# edrschematic.net
KiCad netlist of a schematic drawn in Altium Designer
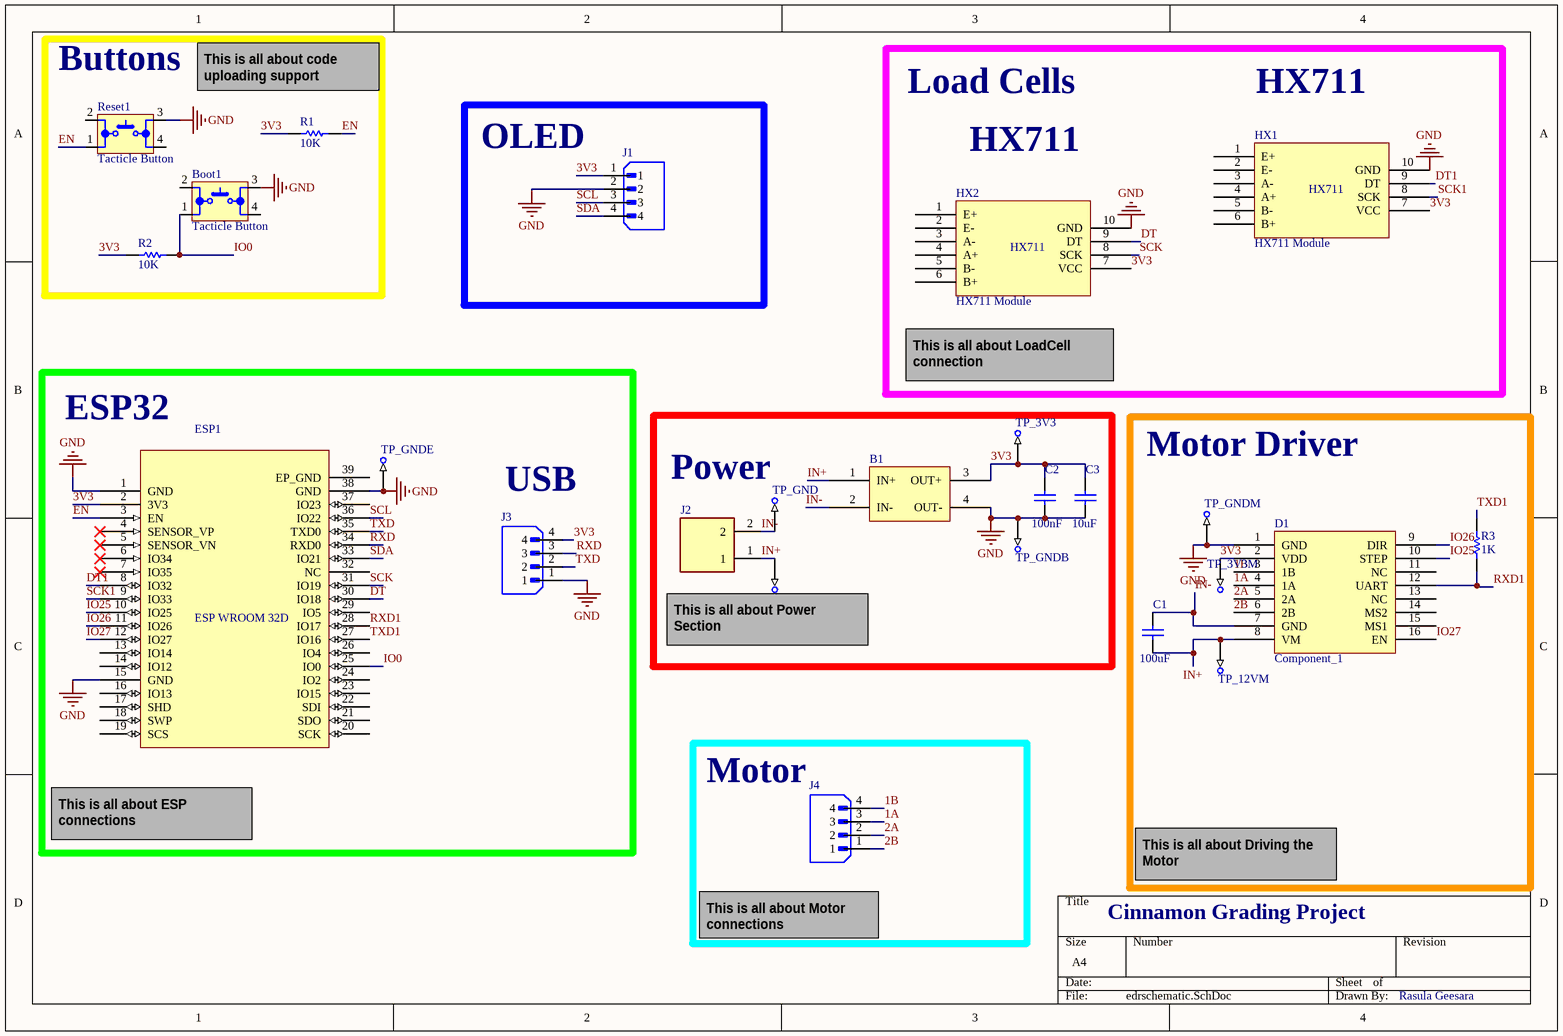
[diagram p0: edrschematic.SchDoc]

(export (version "E")
  (design (tool "Eeschema 10.0.6"))
  (components
    (comp (ref "B1")
      (value "LM2596s Buck")
      (footprint "LM2596s buck:PCBComponent_1")
      (description "buck converter")
      (libsource (lib "LM2596s buck") (part "LM2596s Buck"))
    )
    (comp (ref "Boot1")
      (value "Tacticle Button")
      (footprint "1825910-6_BUTTON")
      (description "SWITCH TACTILE SPST-NO 0.05A 24V")
      (fields
        (field (name "MANUFACTURER") "TE Connectivity Alcoswitch")
        (field (name "MANUFACTURER PART NUMBER") "1825910-6")
      )
      (libsource (lib "Tactile_Switch_Integrated_Library") (part "1825910-6"))
    )
    (comp (ref "C1")
      (value "100uF")
      (footprint "RAD-0.3")
      (description "Capacitor")
      (fields (field (name "Comment") "Cap") (field (name "PUBLISHER") "Altium Limited"))
      (libsource (lib "Miscellaneous Devices") (part "Cap"))
    )
    (comp (ref "C2")
      (value "100nF")
      (footprint "RAD-0.3")
      (description "Capacitor")
      (fields (field (name "Comment") "Cap") (field (name "PUBLISHER") "Altium Limited"))
      (libsource (lib "Miscellaneous Devices") (part "Cap"))
    )
    (comp (ref "C3")
      (value "10uF")
      (footprint "RAD-0.3")
      (description "Capacitor")
      (fields (field (name "Comment") "Cap") (field (name "PUBLISHER") "Altium Limited"))
      (libsource (lib "Miscellaneous Devices") (part "Cap"))
    )
    (comp (ref "D1")
      (value "Component_1")
      (footprint "stepper driver:MODULE_TMC2208_SILENTSTEPSTICK")
      (libsource (lib "stepper driver") (part "Component_1"))
    )
    (comp (ref "ESP1")
      (value "Component_1")
      (footprint "ESP32-WROOM-32D")
      (libsource (lib "Integrated_Library3") (part "Component_1"))
    )
    (comp (ref "HX1")
      (value "HX711 Module")
      (footprint "HX711_NEW:HX711")
      (libsource (lib "Integrated_Library2") (part "HX711"))
    )
    (comp (ref "HX2")
      (value "HX711 Module")
      (footprint "HX711_NEW:HX711")
      (libsource (lib "Integrated_Library2") (part "HX711"))
    )
    (comp (ref "J1")
      (value "B4B-XH-A(LF)(SN)")
      (footprint "B4B-XH-A_LF__SN_:JST_B4B-XH-A(LF)(SN)")
      (description "Connector Header Through Hole 4 position 0.098 (2.50mm)")
      (fields (field (name "MF") "JST Sales"))
      (libsource (lib "") (part "B4B-XH-A(LF)(SN)_1"))
    )
    (comp (ref "J2")
      (value "KF301-2P")
      (footprint "HANDSON_KF301-2P")
      (description "2 Pin Terminal Block 5mm Pitch")
      (fields (field (name "MF") "Handson Technology"))
      (libsource (lib "KF301-2P") (part "KF301-2P"))
    )
    (comp (ref "J3")
      (value "B4B-XH-A(LF)(SN)")
      (footprint "B4B-XH-A_LF__SN_:JST_B4B-XH-A(LF)(SN)")
      (description "Connector Header Through Hole 4 position 0.098 (2.50mm)")
      (fields (field (name "MF") "JST Sales"))
      (libsource (lib "B4B-XH-A_LF__SN_") (part "B4B-XH-A(LF)(SN)"))
    )
    (comp (ref "J4")
      (value "B4B-XH-A(LF)(SN)")
      (footprint "B4B-XH-A_LF__SN_:JST_B4B-XH-A(LF)(SN)")
      (description "Connector Header Through Hole 4 position 0.098 (2.50mm)")
      (fields (field (name "MF") "JST Sales"))
      (libsource (lib "B4B-XH-A_LF__SN_") (part "B4B-XH-A(LF)(SN)"))
    )
    (comp (ref "R1")
      (value "10K")
      (footprint "AXIAL-0.3")
      (description "Resistor")
      (fields (field (name "Comment") "Res1") (field (name "PUBLISHER") "Altium Limited"))
      (libsource (lib "Miscellaneous Devices") (part "Res1"))
    )
    (comp (ref "R2")
      (value "10K")
      (footprint "AXIAL-0.3")
      (description "Resistor")
      (fields (field (name "Comment") "Res1") (field (name "PUBLISHER") "Altium Limited"))
      (libsource (lib "Miscellaneous Devices") (part "Res1"))
    )
    (comp (ref "R3")
      (value "1K")
      (footprint "AXIAL-0.3")
      (description "Resistor")
      (fields (field (name "Comment") "Res1") (field (name "PUBLISHER") "Altium Limited"))
      (libsource (lib "Miscellaneous Devices") (part "Res1"))
    )
    (comp (ref "Reset1")
      (value "Tacticle Button")
      (footprint "1825910-6_BUTTON")
      (description "SWITCH TACTILE SPST-NO 0.05A 24V")
      (fields
        (field (name "MANUFACTURER") "TE Connectivity Alcoswitch")
        (field (name "MANUFACTURER PART NUMBER") "1825910-6")
      )
      (libsource (lib "Tactile_Switch_Integrated_Library") (part "1825910-6"))
    )
    (comp (ref "TP_3V3")
      (value "net?")
      (footprint "MY_Testpad1")
      (description "Test point")
      (fields (field (name "ASID PART NUMBER") "Test Point-AS"))
      (libsource (lib "Mylib+Rev+4") (part "Test Point"))
    )
    (comp (ref "TP_3V3M")
      (value "net?")
      (footprint "MY_Testpad1")
      (description "Test point")
      (fields (field (name "ASID PART NUMBER") "Test Point-AS"))
      (libsource (lib "Mylib+Rev+4") (part "Test Point"))
    )
    (comp (ref "TP_12VM")
      (value "net?")
      (footprint "MY_Testpad1")
      (description "Test point")
      (fields (field (name "ASID PART NUMBER") "Test Point-AS"))
      (libsource (lib "Mylib+Rev+4") (part "Test Point"))
    )
    (comp (ref "TP_BAT")
      (value "net?")
      (footprint "MY_Testpad1")
      (description "Test point")
      (fields (field (name "ASID PART NUMBER") "Test Point-AS"))
      (libsource (lib "Mylib+Rev+4") (part "Test Point"))
    )
    (comp (ref "TP_GND")
      (value "net?")
      (footprint "MY_Testpad1")
      (description "Test point")
      (fields (field (name "ASID PART NUMBER") "Test Point-AS"))
      (libsource (lib "Mylib+Rev+4") (part "Test Point"))
    )
    (comp (ref "TP_GNDB")
      (value "net?")
      (footprint "MY_Testpad1")
      (description "Test point")
      (fields (field (name "ASID PART NUMBER") "Test Point-AS"))
      (libsource (lib "Mylib+Rev+4") (part "Test Point"))
    )
    (comp (ref "TP_GNDE")
      (value "net?")
      (footprint "MY_Testpad1")
      (description "Test point")
      (fields (field (name "ASID PART NUMBER") "Test Point-AS"))
      (libsource (lib "Mylib+Rev+4") (part "Test Point"))
    )
    (comp (ref "TP_GNDM")
      (value "net?")
      (footprint "MY_Testpad1")
      (description "Test point")
      (fields (field (name "ASID PART NUMBER") "Test Point-AS"))
      (libsource (lib "Mylib+Rev+4") (part "Test Point"))
    )
  )
  (nets
    (net (code "1") (name "/1A") (class "Default")
      (node (ref "D1") (pin "4") (pinfunction "1A_4") (pintype "passive"))
      (node (ref "J4") (pin "3") (pinfunction "3_3") (pintype "passive"))
    )
    (net (code "2") (name "/1B") (class "Default")
      (node (ref "D1") (pin "3") (pinfunction "1B_3") (pintype "passive"))
      (node (ref "J4") (pin "4") (pinfunction "4_4") (pintype "passive"))
    )
    (net (code "3") (name "/2A") (class "Default")
      (node (ref "D1") (pin "5") (pinfunction "2A_5") (pintype "passive"))
      (node (ref "J4") (pin "2") (pinfunction "2_2") (pintype "passive"))
    )
    (net (code "4") (name "/2B") (class "Default")
      (node (ref "D1") (pin "6") (pinfunction "2B_6") (pintype "passive"))
      (node (ref "J4") (pin "1") (pinfunction "1_1") (pintype "passive"))
    )
    (net (code "5") (name "/3V3") (class "Default")
      (node (ref "B1") (pin "3") (pinfunction "OUT+_3") (pintype "passive"))
      (node (ref "C2") (pin "2") (pinfunction "2_2") (pintype "passive"))
      (node (ref "C3") (pin "2") (pinfunction "2_2") (pintype "passive"))
      (node (ref "D1") (pin "2") (pinfunction "VDD_2") (pintype "passive"))
      (node (ref "ESP1") (pin "2") (pinfunction "3V3_2") (pintype "passive"))
      (node (ref "HX1") (pin "7") (pinfunction "VCC_7") (pintype "passive"))
      (node (ref "HX2") (pin "7") (pinfunction "VCC_7") (pintype "passive"))
      (node (ref "J1") (pin "1") (pinfunction "1_1") (pintype "passive"))
      (node (ref "J3") (pin "4") (pinfunction "4_4") (pintype "passive"))
      (node (ref "R1") (pin "1") (pinfunction "1_1") (pintype "passive"))
      (node (ref "R2") (pin "1") (pinfunction "1_1") (pintype "passive"))
      (node (ref "TP_3V3") (pin "1") (pinfunction "1_1") (pintype "input"))
      (node (ref "TP_3V3M") (pin "1") (pinfunction "1_1") (pintype "input"))
    )
    (net (code "6") (name "/DT") (class "Default")
      (node (ref "ESP1") (pin "30") (pinfunction "IO18_30") (pintype "bidirectional"))
      (node (ref "HX2") (pin "9") (pinfunction "DT_9") (pintype "passive"))
    )
    (net (code "7") (name "/DT1") (class "Default")
      (node (ref "ESP1") (pin "8") (pinfunction "IO32_8") (pintype "bidirectional"))
      (node (ref "HX1") (pin "9") (pinfunction "DT_9") (pintype "passive"))
    )
    (net (code "8") (name "/EN") (class "Default")
      (node (ref "ESP1") (pin "3") (pinfunction "EN_3") (pintype "input"))
      (node (ref "R1") (pin "2") (pinfunction "2_2") (pintype "passive"))
      (node (ref "Reset1") (pin "1") (pinfunction "1_1") (pintype "passive"))
    )
    (net (code "9") (name "/IN+") (class "Default")
      (node (ref "B1") (pin "1") (pinfunction "IN+_1") (pintype "passive"))
      (node (ref "C1") (pin "1") (pinfunction "1_1") (pintype "passive"))
      (node (ref "D1") (pin "8") (pinfunction "VM_8") (pintype "passive"))
      (node (ref "J2") (pin "1") (pinfunction "1_1") (pintype "passive"))
      (node (ref "TP_12VM") (pin "1") (pinfunction "1_1") (pintype "input"))
      (node (ref "TP_BAT") (pin "1") (pinfunction "1_1") (pintype "input"))
    )
    (net (code "10") (name "/IN-") (class "Default")
      (node (ref "B1") (pin "2") (pinfunction "IN-_2") (pintype "passive"))
      (node (ref "C1") (pin "2") (pinfunction "2_2") (pintype "passive"))
      (node (ref "D1") (pin "7") (pinfunction "GND_7") (pintype "passive"))
      (node (ref "J2") (pin "2") (pinfunction "2_2") (pintype "passive"))
      (node (ref "TP_GND") (pin "1") (pinfunction "1_1") (pintype "input"))
    )
    (net (code "11") (name "/IO0") (class "Default")
      (node (ref "Boot1") (pin "1") (pinfunction "1_1") (pintype "passive"))
      (node (ref "ESP1") (pin "25") (pinfunction "IO0_25") (pintype "bidirectional"))
      (node (ref "R2") (pin "2") (pinfunction "2_2") (pintype "passive"))
    )
    (net (code "12") (name "/IO25") (class "Default")
      (node (ref "D1") (pin "10") (pinfunction "STEP_10") (pintype "passive"))
      (node (ref "ESP1") (pin "10") (pinfunction "IO25_10") (pintype "bidirectional"))
    )
    (net (code "13") (name "/IO26") (class "Default")
      (node (ref "D1") (pin "9") (pinfunction "DIR_9") (pintype "passive"))
      (node (ref "ESP1") (pin "11") (pinfunction "IO26_11") (pintype "bidirectional"))
    )
    (net (code "14") (name "/IO27") (class "Default")
      (node (ref "D1") (pin "16") (pinfunction "EN_16") (pintype "passive"))
      (node (ref "ESP1") (pin "12") (pinfunction "IO27_12") (pintype "bidirectional"))
    )
    (net (code "15") (name "/RXD") (class "Default")
      (node (ref "ESP1") (pin "34") (pinfunction "RXD0_34") (pintype "bidirectional"))
      (node (ref "J3") (pin "3") (pinfunction "3_3") (pintype "passive"))
    )
    (net (code "16") (name "/RXD1") (class "Default")
      (node (ref "D1") (pin "12") (pinfunction "UART_12") (pintype "passive"))
      (node (ref "ESP1") (pin "28") (pinfunction "IO17_28") (pintype "bidirectional"))
      (node (ref "R3") (pin "1") (pinfunction "1_1") (pintype "passive"))
    )
    (net (code "17") (name "/SCK") (class "Default")
      (node (ref "ESP1") (pin "31") (pinfunction "IO19_31") (pintype "bidirectional"))
      (node (ref "HX2") (pin "8") (pinfunction "SCK_8") (pintype "passive"))
    )
    (net (code "18") (name "/SCK1") (class "Default")
      (node (ref "ESP1") (pin "9") (pinfunction "IO33_9") (pintype "bidirectional"))
      (node (ref "HX1") (pin "8") (pinfunction "SCK_8") (pintype "passive"))
    )
    (net (code "19") (name "/SCL") (class "Default")
      (node (ref "ESP1") (pin "36") (pinfunction "IO22_36") (pintype "bidirectional"))
      (node (ref "J1") (pin "3") (pinfunction "3_3") (pintype "passive"))
    )
    (net (code "20") (name "/SDA") (class "Default")
      (node (ref "ESP1") (pin "33") (pinfunction "IO21_33") (pintype "bidirectional"))
      (node (ref "J1") (pin "4") (pinfunction "4_4") (pintype "passive"))
    )
    (net (code "21") (name "/TXD") (class "Default")
      (node (ref "ESP1") (pin "35") (pinfunction "TXD0_35") (pintype "bidirectional"))
      (node (ref "J3") (pin "2") (pinfunction "2_2") (pintype "passive"))
    )
    (net (code "22") (name "/TXD1") (class "Default")
      (node (ref "ESP1") (pin "27") (pinfunction "IO16_27") (pintype "bidirectional"))
      (node (ref "R3") (pin "2") (pinfunction "2_2") (pintype "passive"))
    )
    (net (code "23") (name "GND") (class "Default")
      (node (ref "B1") (pin "4") (pinfunction "OUT-_4") (pintype "passive"))
      (node (ref "Boot1") (pin "3") (pinfunction "3_3") (pintype "passive"))
      (node (ref "C2") (pin "1") (pinfunction "1_1") (pintype "passive"))
      (node (ref "C3") (pin "1") (pinfunction "1_1") (pintype "passive"))
      (node (ref "D1") (pin "1") (pinfunction "GND_1") (pintype "passive"))
      (node (ref "ESP1") (pin "1") (pinfunction "GND_1") (pintype "passive"))
      (node (ref "ESP1") (pin "15") (pinfunction "GND_15") (pintype "passive"))
      (node (ref "ESP1") (pin "38") (pinfunction "GND_38") (pintype "passive"))
      (node (ref "HX1") (pin "10") (pinfunction "GND_10") (pintype "passive"))
      (node (ref "HX2") (pin "10") (pinfunction "GND_10") (pintype "passive"))
      (node (ref "J1") (pin "2") (pinfunction "2_2") (pintype "passive"))
      (node (ref "J3") (pin "1") (pinfunction "1_1") (pintype "passive"))
      (node (ref "Reset1") (pin "3") (pinfunction "3_3") (pintype "passive"))
      (node (ref "TP_GNDB") (pin "1") (pinfunction "1_1") (pintype "input"))
      (node (ref "TP_GNDE") (pin "1") (pinfunction "1_1") (pintype "input"))
      (node (ref "TP_GNDM") (pin "1") (pinfunction "1_1") (pintype "input"))
    )
    (net (code "24") (name "unconnected-(Boot1-Pad2)") (class "Default")
      (node (ref "Boot1") (pin "2") (pinfunction "2_2") (pintype "passive"))
    )
    (net (code "25") (name "unconnected-(Boot1-Pad4)") (class "Default")
      (node (ref "Boot1") (pin "4") (pinfunction "4_4") (pintype "passive"))
    )
    (net (code "26") (name "unconnected-(D1-MS1-Pad15)") (class "Default")
      (node (ref "D1") (pin "15") (pinfunction "MS1_15") (pintype "passive"))
    )
    (net (code "27") (name "unconnected-(D1-MS2-Pad14)") (class "Default")
      (node (ref "D1") (pin "14") (pinfunction "MS2_14") (pintype "passive"))
    )
    (net (code "28") (name "unconnected-(D1-NC-Pad11)") (class "Default")
      (node (ref "D1") (pin "11") (pinfunction "NC_11") (pintype "passive"))
    )
    (net (code "29") (name "unconnected-(D1-NC-Pad13)") (class "Default")
      (node (ref "D1") (pin "13") (pinfunction "NC_13") (pintype "passive"))
    )
    (net (code "30") (name "unconnected-(ESP1-EP_GND-Pad39)") (class "Default")
      (node (ref "ESP1") (pin "39") (pinfunction "EP_GND_39") (pintype "passive"))
    )
    (net (code "31") (name "unconnected-(ESP1-IO2-Pad24)") (class "Default")
      (node (ref "ESP1") (pin "24") (pinfunction "IO2_24") (pintype "bidirectional"))
    )
    (net (code "32") (name "unconnected-(ESP1-IO4-Pad26)") (class "Default")
      (node (ref "ESP1") (pin "26") (pinfunction "IO4_26") (pintype "bidirectional"))
    )
    (net (code "33") (name "unconnected-(ESP1-IO5-Pad29)") (class "Default")
      (node (ref "ESP1") (pin "29") (pinfunction "IO5_29") (pintype "bidirectional"))
    )
    (net (code "34") (name "unconnected-(ESP1-IO12-Pad14)") (class "Default")
      (node (ref "ESP1") (pin "14") (pinfunction "IO12_14") (pintype "bidirectional"))
    )
    (net (code "35") (name "unconnected-(ESP1-IO13-Pad16)") (class "Default")
      (node (ref "ESP1") (pin "16") (pinfunction "IO13_16") (pintype "bidirectional"))
    )
    (net (code "36") (name "unconnected-(ESP1-IO14-Pad13)") (class "Default")
      (node (ref "ESP1") (pin "13") (pinfunction "IO14_13") (pintype "bidirectional"))
    )
    (net (code "37") (name "unconnected-(ESP1-IO15-Pad23)") (class "Default")
      (node (ref "ESP1") (pin "23") (pinfunction "IO15_23") (pintype "bidirectional"))
    )
    (net (code "38") (name "unconnected-(ESP1-IO23-Pad37)") (class "Default")
      (node (ref "ESP1") (pin "37") (pinfunction "IO23_37") (pintype "bidirectional"))
    )
    (net (code "39") (name "unconnected-(ESP1-IO34-Pad6)") (class "Default")
      (node (ref "ESP1") (pin "6") (pinfunction "IO34_6") (pintype "input+no_connect"))
    )
    (net (code "40") (name "unconnected-(ESP1-IO35-Pad7)") (class "Default")
      (node (ref "ESP1") (pin "7") (pinfunction "IO35_7") (pintype "input+no_connect"))
    )
    (net (code "41") (name "unconnected-(ESP1-NC-Pad32)") (class "Default")
      (node (ref "ESP1") (pin "32") (pinfunction "NC_32") (pintype "passive"))
    )
    (net (code "42") (name "unconnected-(ESP1-SCK-Pad20)") (class "Default")
      (node (ref "ESP1") (pin "20") (pinfunction "SCK_20") (pintype "bidirectional"))
    )
    (net (code "43") (name "unconnected-(ESP1-SCS-Pad19)") (class "Default")
      (node (ref "ESP1") (pin "19") (pinfunction "SCS_19") (pintype "bidirectional"))
    )
    (net (code "44") (name "unconnected-(ESP1-SDI-Pad22)") (class "Default")
      (node (ref "ESP1") (pin "22") (pinfunction "SDI_22") (pintype "bidirectional"))
    )
    (net (code "45") (name "unconnected-(ESP1-SDO-Pad21)") (class "Default")
      (node (ref "ESP1") (pin "21") (pinfunction "SDO_21") (pintype "bidirectional"))
    )
    (net (code "46") (name "unconnected-(ESP1-SENSOR_VN-Pad5)") (class "Default")
      (node (ref "ESP1") (pin "5") (pinfunction "SENSOR_VN_5") (pintype "input+no_connect"))
    )
    (net (code "47") (name "unconnected-(ESP1-SENSOR_VP-Pad4)") (class "Default")
      (node (ref "ESP1") (pin "4") (pinfunction "SENSOR_VP_4") (pintype "input+no_connect"))
    )
    (net (code "48") (name "unconnected-(ESP1-SHD-Pad17)") (class "Default")
      (node (ref "ESP1") (pin "17") (pinfunction "SHD_17") (pintype "bidirectional"))
    )
    (net (code "49") (name "unconnected-(ESP1-SWP-Pad18)") (class "Default")
      (node (ref "ESP1") (pin "18") (pinfunction "SWP_18") (pintype "bidirectional"))
    )
    (net (code "50") (name "unconnected-(HX1-A+-Pad4)") (class "Default")
      (node (ref "HX1") (pin "4") (pinfunction "A+_4") (pintype "passive"))
    )
    (net (code "51") (name "unconnected-(HX1-A--Pad3)") (class "Default")
      (node (ref "HX1") (pin "3") (pinfunction "A-_3") (pintype "passive"))
    )
    (net (code "52") (name "unconnected-(HX1-B+-Pad6)") (class "Default")
      (node (ref "HX1") (pin "6") (pinfunction "B+_6") (pintype "passive"))
    )
    (net (code "53") (name "unconnected-(HX1-B--Pad5)") (class "Default")
      (node (ref "HX1") (pin "5") (pinfunction "B-_5") (pintype "passive"))
    )
    (net (code "54") (name "unconnected-(HX1-E+-Pad1)") (class "Default")
      (node (ref "HX1") (pin "1") (pinfunction "E+_1") (pintype "passive"))
    )
    (net (code "55") (name "unconnected-(HX1-E--Pad2)") (class "Default")
      (node (ref "HX1") (pin "2") (pinfunction "E-_2") (pintype "passive"))
    )
    (net (code "56") (name "unconnected-(HX2-A+-Pad4)") (class "Default")
      (node (ref "HX2") (pin "4") (pinfunction "A+_4") (pintype "passive"))
    )
    (net (code "57") (name "unconnected-(HX2-A--Pad3)") (class "Default")
      (node (ref "HX2") (pin "3") (pinfunction "A-_3") (pintype "passive"))
    )
    (net (code "58") (name "unconnected-(HX2-B+-Pad6)") (class "Default")
      (node (ref "HX2") (pin "6") (pinfunction "B+_6") (pintype "passive"))
    )
    (net (code "59") (name "unconnected-(HX2-B--Pad5)") (class "Default")
      (node (ref "HX2") (pin "5") (pinfunction "B-_5") (pintype "passive"))
    )
    (net (code "60") (name "unconnected-(HX2-E+-Pad1)") (class "Default")
      (node (ref "HX2") (pin "1") (pinfunction "E+_1") (pintype "passive"))
    )
    (net (code "61") (name "unconnected-(HX2-E--Pad2)") (class "Default")
      (node (ref "HX2") (pin "2") (pinfunction "E-_2") (pintype "passive"))
    )
    (net (code "62") (name "unconnected-(Reset1-Pad2)") (class "Default")
      (node (ref "Reset1") (pin "2") (pinfunction "2_2") (pintype "passive"))
    )
    (net (code "63") (name "unconnected-(Reset1-Pad4)") (class "Default")
      (node (ref "Reset1") (pin "4") (pinfunction "4_4") (pintype "passive"))
    )
  )
)
